# InputConnectors.net
KiCad netlist of a schematic drawn in Altium Designer
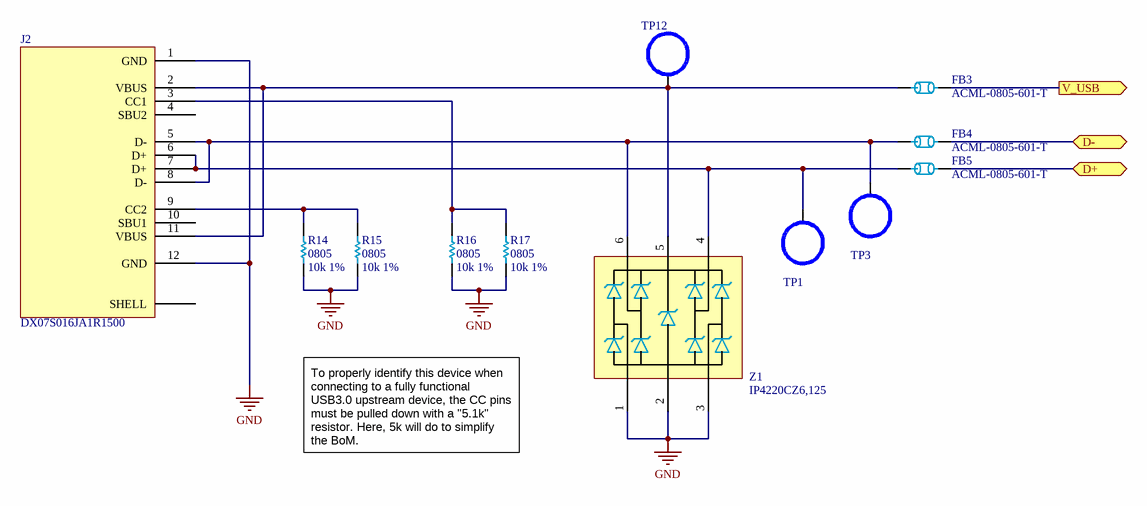
[diagram p0: InputConnectors.SchDoc]

(export (version "E")
  (design (tool "Eeschema 10.0.6"))
  (components
    (comp (ref "FB3")
      (value "ACML-0805-601-T")
      (footprint "0805")
      (description "FERRITE BEAD 600 OHM 0805 1LN")
      (libsource (lib "Chip_Passives") (part "ACML-0805-601-T"))
    )
    (comp (ref "FB4")
      (value "ACML-0805-601-T")
      (footprint "0805")
      (description "FERRITE BEAD 600 OHM 0805 1LN")
      (libsource (lib "Chip_Passives") (part "ACML-0805-601-T"))
    )
    (comp (ref "FB5")
      (value "ACML-0805-601-T")
      (footprint "0805")
      (description "FERRITE BEAD 600 OHM 0805 1LN")
      (libsource (lib "Chip_Passives") (part "ACML-0805-601-T"))
    )
    (comp (ref "J2")
      (value "DX07S016JA1R1500")
      (footprint "DX07S016JA1R1500")
      (libsource (lib "Connectors") (part "DX07S016JA1R1500"))
    )
    (comp (ref "R14")
      (value "0805")
      (footprint "0805")
      (description "Chip resistor")
      (fields (field (name "ALTIUM_VALUE") "10k 1%"))
      (libsource (lib "Chip_Passives") (part "Res 10k 1% 0805"))
    )
    (comp (ref "R15")
      (value "0805")
      (footprint "0805")
      (description "Chip resistor")
      (fields (field (name "ALTIUM_VALUE") "10k 1%"))
      (libsource (lib "Chip_Passives") (part "Res 10k 1% 0805"))
    )
    (comp (ref "R16")
      (value "0805")
      (footprint "0805")
      (description "Chip resistor")
      (fields (field (name "ALTIUM_VALUE") "10k 1%"))
      (libsource (lib "Chip_Passives") (part "Res 10k 1% 0805"))
    )
    (comp (ref "R17")
      (value "0805")
      (footprint "0805")
      (description "Chip resistor")
      (fields (field (name "ALTIUM_VALUE") "10k 1%"))
      (libsource (lib "Chip_Passives") (part "Res 10k 1% 0805"))
    )
    (comp (ref "TP1")
      (value "TestPointHook")
      (footprint "S2751-46R")
      (description "Test point, SMT ring (micro-hook compatible)")
      (libsource (lib "PCBFeatures") (part "TestPointHook"))
    )
    (comp (ref "TP3")
      (value "TestPointHook")
      (footprint "S2751-46R")
      (description "Test point, SMT ring (micro-hook compatible)")
      (libsource (lib "PCBFeatures") (part "TestPointHook"))
    )
    (comp (ref "TP12")
      (value "TestPointHook")
      (footprint "S2751-46R")
      (description "Test point, SMT ring (micro-hook compatible)")
      (libsource (lib "PCBFeatures") (part "TestPointHook"))
    )
    (comp (ref "Z1")
      (value "IP4220CZ6,125")
      (footprint "PESD3V3S4UD - SOT95P275X110-6N")
      (description "TVS DIODE 5.5V 6TSOP (Low capacitance, USB)")
      (libsource (lib "Diodes") (part "IP4220CZ6,125"))
    )
  )
  (nets
    (net (code "1") (name "/D+") (class "Default")
      (node (ref "FB5") (pin "2") (pinfunction "2_2") (pintype "passive"))
    )
    (net (code "2") (name "/D-") (class "Default")
      (node (ref "FB4") (pin "2") (pinfunction "2_2") (pintype "passive"))
    )
    (net (code "3") (name "/V_USB") (class "Default")
      (node (ref "FB3") (pin "2") (pinfunction "2_2") (pintype "passive"))
    )
    (net (code "4") (name "GND") (class "Default")
      (node (ref "J2") (pin "1") (pinfunction "GND_1") (pintype "passive"))
      (node (ref "J2") (pin "12") (pinfunction "GND_12") (pintype "passive"))
      (node (ref "R14") (pin "1") (pinfunction "1_1") (pintype "passive"))
      (node (ref "R15") (pin "1") (pinfunction "1_1") (pintype "passive"))
      (node (ref "R16") (pin "1") (pinfunction "1_1") (pintype "passive"))
      (node (ref "R17") (pin "1") (pinfunction "1_1") (pintype "passive"))
      (node (ref "Z1") (pin "1") (pinfunction "1_1") (pintype "passive"))
      (node (ref "Z1") (pin "2") (pinfunction "2_2") (pintype "passive"))
      (node (ref "Z1") (pin "3") (pinfunction "3_3") (pintype "passive"))
    )
    (net (code "5") (name "Net-(FB3-Pad1)") (class "Default")
      (node (ref "FB3") (pin "1") (pinfunction "1_1") (pintype "passive"))
      (node (ref "J2") (pin "11") (pinfunction "VBUS_11") (pintype "passive"))
      (node (ref "J2") (pin "2") (pinfunction "VBUS_2") (pintype "passive"))
      (node (ref "TP12") (pin "1") (pinfunction "1_1") (pintype "passive"))
      (node (ref "Z1") (pin "5") (pinfunction "5_5") (pintype "passive"))
    )
    (net (code "6") (name "Net-(FB4-Pad1)") (class "Default")
      (node (ref "FB4") (pin "1") (pinfunction "1_1") (pintype "passive"))
      (node (ref "J2") (pin "5") (pinfunction "D-_5") (pintype "passive"))
      (node (ref "J2") (pin "8") (pinfunction "D-_8") (pintype "passive"))
      (node (ref "TP3") (pin "1") (pinfunction "1_1") (pintype "passive"))
      (node (ref "Z1") (pin "6") (pinfunction "6_6") (pintype "passive"))
    )
    (net (code "7") (name "Net-(FB5-Pad1)") (class "Default")
      (node (ref "FB5") (pin "1") (pinfunction "1_1") (pintype "passive"))
      (node (ref "J2") (pin "6") (pinfunction "D+_6") (pintype "passive"))
      (node (ref "J2") (pin "7") (pinfunction "D+_7") (pintype "passive"))
      (node (ref "TP1") (pin "1") (pinfunction "1_1") (pintype "passive"))
      (node (ref "Z1") (pin "4") (pinfunction "4_4") (pintype "passive"))
    )
    (net (code "8") (name "Net-(J2-CC1)") (class "Default")
      (node (ref "J2") (pin "3") (pinfunction "CC1_3") (pintype "passive"))
      (node (ref "R16") (pin "2") (pinfunction "2_2") (pintype "passive"))
      (node (ref "R17") (pin "2") (pinfunction "2_2") (pintype "passive"))
    )
    (net (code "9") (name "Net-(J2-CC2)") (class "Default")
      (node (ref "J2") (pin "9") (pinfunction "CC2_9") (pintype "passive"))
      (node (ref "R14") (pin "2") (pinfunction "2_2") (pintype "passive"))
      (node (ref "R15") (pin "2") (pinfunction "2_2") (pintype "passive"))
    )
    (net (code "10") (name "unconnected-(J2-PadSHELL)") (class "Default")
      (node (ref "J2") (pin "SHELL") (pinfunction "SHELL_SHELL") (pintype "passive"))
    )
    (net (code "11") (name "unconnected-(J2-SBU1-Pad10)") (class "Default")
      (node (ref "J2") (pin "10") (pinfunction "SBU1_10") (pintype "passive"))
    )
    (net (code "12") (name "unconnected-(J2-SBU2-Pad4)") (class "Default")
      (node (ref "J2") (pin "4") (pinfunction "SBU2_4") (pintype "passive"))
    )
  )
)
